# LDOs.net
KiCad netlist of a schematic drawn in Altium Designer
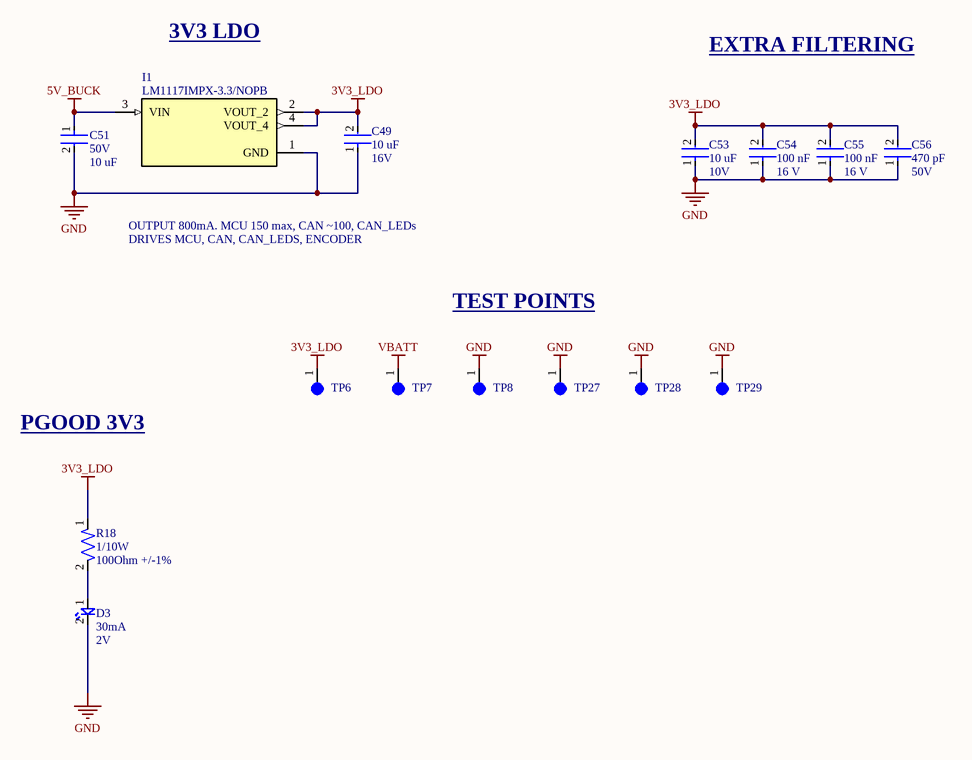
[diagram p0: LDOs.SchDoc]

(export (version "E")
  (design (tool "Eeschema 10.0.6"))
  (components
    (comp (ref "C49")
      (value "293D106X9016A2TE3")
      (footprint "MasterLib:CAP-1210")
      (description "CAP TANT 10UF 10% 16V 1206")
      (fields (field (name "VOLTAGE") "16V") (field (name "CAPACITANCE") "10 uF"))
      (libsource (lib "JLC_25") (part "CAP-10U-0003"))
    )
    (comp (ref "C51")
      (value "CL32B106KBJNNNE")
      (footprint "CAP-1210")
      (description "CAP CER 10UF 50V X7R 1210")
      (fields (field (name "VOLTAGE") "50V") (field (name "CAPACITANCE") "10 uF"))
      (libsource (lib "JLC_25") (part "CAP-10U-0002"))
    )
    (comp (ref "C53")
      (value "CC0603KRX5R6BB106")
      (footprint "CAP-0603")
      (description "CAP CER 10UF 10V X5R 0603")
      (fields (field (name "VOLTAGE") "10V") (field (name "CAPACITANCE") "10 uF"))
      (libsource (lib "JLC_25") (part "CAP-10U-0001"))
    )
    (comp (ref "C54")
      (value "CC0402KRX7R7BB104")
      (footprint "CAP-0402")
      (description "CAP CER 0.1UF 16V X7R 0402")
      (fields (field (name "VOLTAGE RATING") "16 V") (field (name "CAPACITANCE") "100 nF"))
      (libsource (lib "JLC_25") (part "CAP-0.1U-0001"))
    )
    (comp (ref "C55")
      (value "CC0402KRX7R7BB104")
      (footprint "CAP-0402")
      (description "CAP CER 0.1UF 16V X7R 0402")
      (fields (field (name "VOLTAGE RATING") "16 V") (field (name "CAPACITANCE") "100 nF"))
      (libsource (lib "JLC_25") (part "CAP-0.1U-0001"))
    )
    (comp (ref "C56")
      (value "CC0805JRNPO9BN471")
      (footprint "CAP-0805")
      (description "CAP CER 470PF 50V C0G/NPO 0805")
      (fields (field (name "VOLTAGE") "50V") (field (name "CAPACITANCE") "470 pF"))
      (libsource (lib "JLC_25") (part "CAP-470P-0001"))
    )
    (comp (ref "D3")
      (value "BL-HKC36G-AV-TRB")
      (footprint "LED-0603")
      (description "LED YELLOW CLEAR 0603 SMD")
      (fields (field (name "FORWARD CURRENT") "30mA") (field (name "FORWARD VOLTAGE") "2V"))
      (libsource (lib "JLC_25") (part "LED-0001"))
    )
    (comp (ref "I1")
      (value "LM1117IMPX-3.3/NOPB")
      (footprint "IC-SOT-223-4")
      (description "IC REG LIN 3.3V 800MA SOT223-4")
      (libsource (lib "JLC_25") (part "IC_LDO_3V3_0001"))
    )
    (comp (ref "R18")
      (value "AC0603FR-10100RL")
      (footprint "RES-0603")
      (description "100 Ohms ±1% 0.1W, 1/10W Chip Resistor 0603 (1608 Metric) Automotive AEC-Q200 Thick Film")
      (fields
        (field (name "MANUFACTURER") "YAGEO")
        (field (name "POWER RATING") "1/10W")
        (field (name "RESISTANCE") "100Ohm +/-1%")
      )
      (libsource (lib "MasterLib") (part "RES-100-0002"))
    )
    (comp (ref "TP6")
      (value "5003")
      (footprint "TEST-POINT-0001")
      (description "Oranange PC Test Point, Miniature Phoisphor Bronze Silver Plating Through Hole Mounting Type")
      (libsource (lib "JLC_25") (part "TEST-POINT-0001"))
    )
    (comp (ref "TP7")
      (value "5003")
      (footprint "TEST-POINT-0001")
      (description "Oranange PC Test Point, Miniature Phoisphor Bronze Silver Plating Through Hole Mounting Type")
      (libsource (lib "JLC_25") (part "TEST-POINT-0001"))
    )
    (comp (ref "TP8")
      (value "5003")
      (footprint "TEST-POINT-0001")
      (description "Oranange PC Test Point, Miniature Phoisphor Bronze Silver Plating Through Hole Mounting Type")
      (libsource (lib "JLC_25") (part "TEST-POINT-0001"))
    )
    (comp (ref "TP27")
      (value "5003")
      (footprint "TEST-POINT-0001")
      (description "Oranange PC Test Point, Miniature Phoisphor Bronze Silver Plating Through Hole Mounting Type")
      (libsource (lib "JLC_25") (part "TEST-POINT-0001"))
    )
    (comp (ref "TP28")
      (value "5003")
      (footprint "TEST-POINT-0001")
      (description "Oranange PC Test Point, Miniature Phoisphor Bronze Silver Plating Through Hole Mounting Type")
      (libsource (lib "JLC_25") (part "TEST-POINT-0001"))
    )
    (comp (ref "TP29")
      (value "5003")
      (footprint "TEST-POINT-0001")
      (description "Oranange PC Test Point, Miniature Phoisphor Bronze Silver Plating Through Hole Mounting Type")
      (libsource (lib "JLC_25") (part "TEST-POINT-0001"))
    )
  )
  (nets
    (net (code "1") (name "3V3_LDO") (class "Default")
      (node (ref "C49") (pin "2") (pinfunction "2_2") (pintype "passive"))
      (node (ref "C53") (pin "2") (pinfunction "2_2") (pintype "passive"))
      (node (ref "C54") (pin "2") (pinfunction "2_2") (pintype "passive"))
      (node (ref "C55") (pin "2") (pinfunction "2_2") (pintype "passive"))
      (node (ref "C56") (pin "2") (pinfunction "2_2") (pintype "passive"))
      (node (ref "I1") (pin "2") (pinfunction "VOUT_2_2") (pintype "output"))
      (node (ref "I1") (pin "4") (pinfunction "VOUT_4_4") (pintype "output"))
      (node (ref "R18") (pin "1") (pinfunction "1_1") (pintype "passive"))
      (node (ref "TP6") (pin "1") (pinfunction "0_1") (pintype "passive"))
    )
    (net (code "2") (name "5V_BUCK") (class "Default")
      (node (ref "C51") (pin "1") (pinfunction "1_1") (pintype "passive"))
      (node (ref "I1") (pin "3") (pinfunction "VIN_3") (pintype "input"))
    )
    (net (code "3") (name "GND") (class "Default")
      (node (ref "C49") (pin "1") (pinfunction "1_1") (pintype "passive"))
      (node (ref "C51") (pin "2") (pinfunction "2_2") (pintype "passive"))
      (node (ref "C53") (pin "1") (pinfunction "1_1") (pintype "passive"))
      (node (ref "C54") (pin "1") (pinfunction "1_1") (pintype "passive"))
      (node (ref "C55") (pin "1") (pinfunction "1_1") (pintype "passive"))
      (node (ref "C56") (pin "1") (pinfunction "1_1") (pintype "passive"))
      (node (ref "D3") (pin "2") (pinfunction "2_2") (pintype "passive"))
      (node (ref "I1") (pin "1") (pinfunction "GND_1") (pintype "power_in"))
      (node (ref "TP27") (pin "1") (pinfunction "0_1") (pintype "passive"))
      (node (ref "TP28") (pin "1") (pinfunction "0_1") (pintype "passive"))
      (node (ref "TP29") (pin "1") (pinfunction "0_1") (pintype "passive"))
      (node (ref "TP8") (pin "1") (pinfunction "0_1") (pintype "passive"))
    )
    (net (code "4") (name "Net-(D3-Pad1)") (class "Default")
      (node (ref "D3") (pin "1") (pinfunction "1_1") (pintype "passive"))
      (node (ref "R18") (pin "2") (pinfunction "2_2") (pintype "passive"))
    )
    (net (code "5") (name "VBATT") (class "Default")
      (node (ref "TP7") (pin "1") (pinfunction "0_1") (pintype "passive"))
    )
  )
)
